# Titan_VCO.net
KiCad netlist of a schematic drawn in Altium Designer
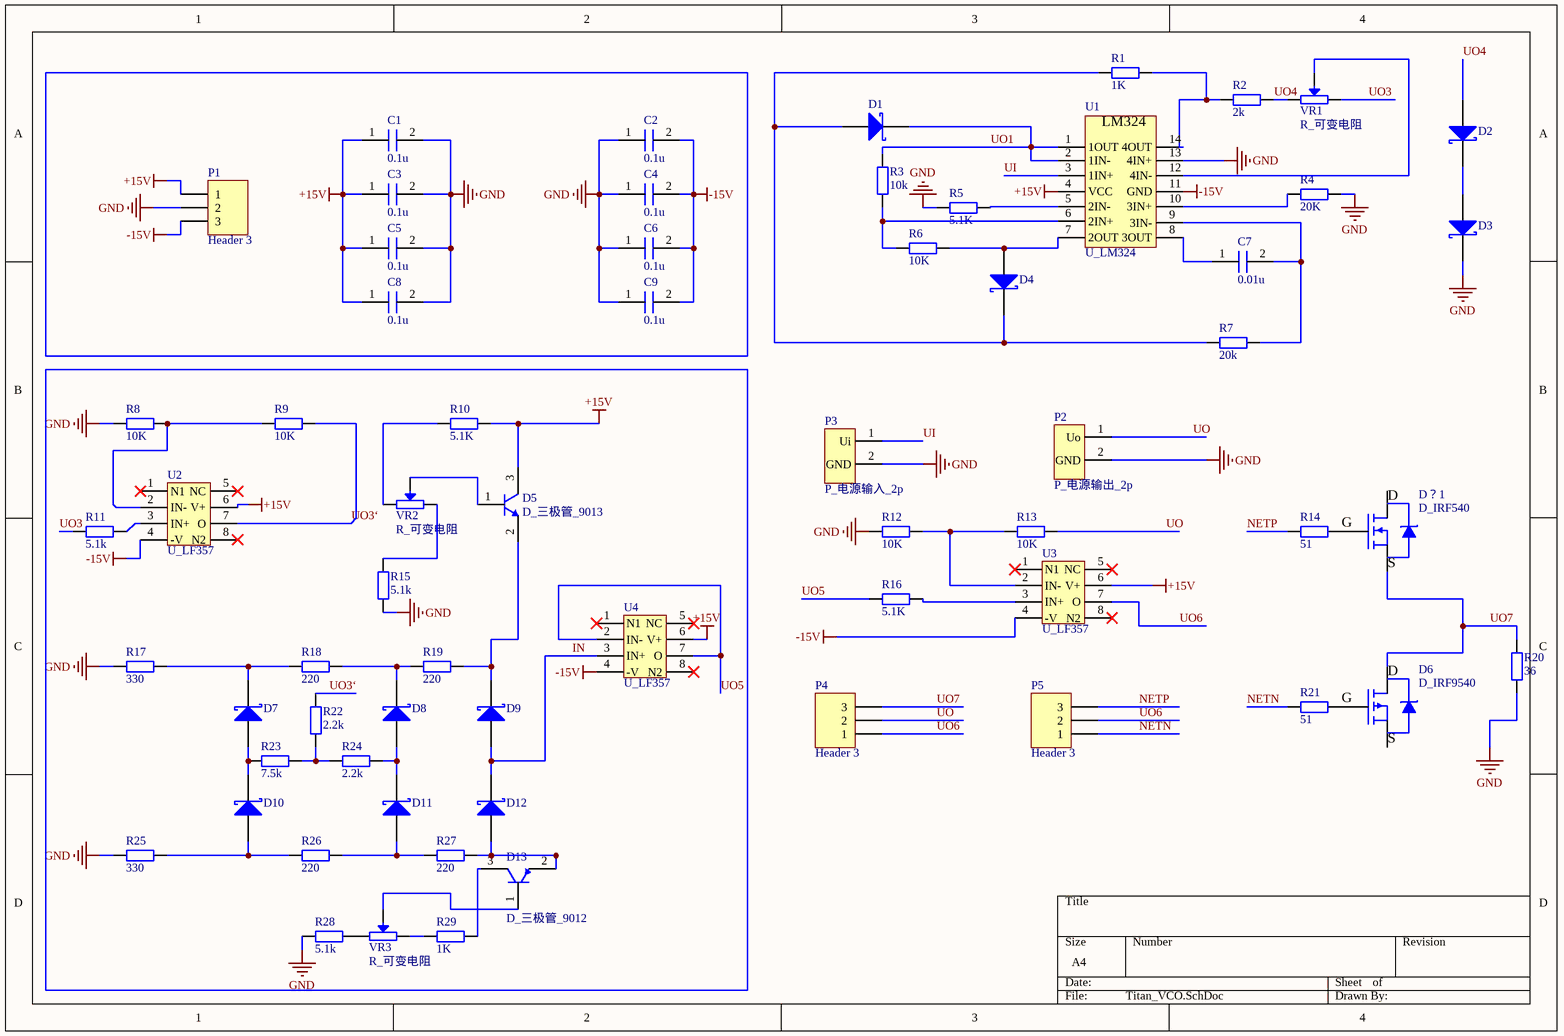
[diagram p0: Titan_VCO.SchDoc]

(export (version "E")
  (design (tool "Eeschema 10.0.6"))
  (components
    (comp (ref "C1") (value "0.1u") (footprint "C 0805_M") (libsource (lib "Titan_Schlib1") (part "C")))
    (comp (ref "C2") (value "0.1u") (footprint "C 0805_M") (libsource (lib "Titan_Schlib1") (part "C")))
    (comp (ref "C3") (value "0.1u") (footprint "C 0805_M") (libsource (lib "Titan_Schlib1") (part "C")))
    (comp (ref "C4") (value "0.1u") (footprint "C 0805_M") (libsource (lib "Titan_Schlib1") (part "C")))
    (comp (ref "C5") (value "0.1u") (footprint "C 0805_M") (libsource (lib "Titan_Schlib1") (part "C")))
    (comp (ref "C6") (value "0.1u") (footprint "C 0805_M") (libsource (lib "Titan_Schlib1") (part "C")))
    (comp (ref "C7") (value "0.01u") (footprint "C 0805_M") (libsource (lib "Titan_Schlib1") (part "C")))
    (comp (ref "C8") (value "0.1u") (footprint "C 0805_M") (libsource (lib "Titan_Schlib1") (part "C")))
    (comp (ref "C9") (value "0.1u") (footprint "C 0805_M") (libsource (lib "Titan_Schlib1") (part "C")))
    (comp (ref "D1")
      (value "D_肖特基管_稳压管")
      (footprint "TO-220AC")
      (description "Schottky Rectifier")
      (fields (field (name "PUBLISHER") "Altium Limited"))
      (libsource (lib "Titan_Schlib1") (part "D_肖特基管_稳压管"))
    )
    (comp (ref "D2")
      (value "D_肖特基管_稳压管")
      (footprint "TO-220AC")
      (description "Schottky Rectifier")
      (fields (field (name "PUBLISHER") "Altium Limited"))
      (libsource (lib "Titan_Schlib1") (part "D_肖特基管_稳压管"))
    )
    (comp (ref "D3")
      (value "D_肖特基管_稳压管")
      (footprint "TO-220AC")
      (description "Schottky Rectifier")
      (fields (field (name "PUBLISHER") "Altium Limited"))
      (libsource (lib "Titan_Schlib1") (part "D_肖特基管_稳压管"))
    )
    (comp (ref "D4")
      (value "D_肖特基管_稳压管")
      (footprint "TO-220AC")
      (description "Schottky Rectifier")
      (fields (field (name "PUBLISHER") "Altium Limited"))
      (libsource (lib "Titan_Schlib1") (part "D_肖特基管_稳压管"))
    )
    (comp (ref "D5")
      (value "D_三极管_9013")
      (footprint "D_三极管_9013")
      (libsource (lib "Titan_Schlib1") (part "D_三极管_9012"))
    )
    (comp (ref "D6")
      (value "D_IRF9540")
      (footprint "D_IRF9540")
      (libsource (lib "Titan_Schlib1") (part "D_IRF9540"))
    )
    (comp (ref "D7")
      (value "D_肖特基管_稳压管")
      (footprint "TO-220AC")
      (description "Schottky Rectifier")
      (fields (field (name "PUBLISHER") "Altium Limited"))
      (libsource (lib "Titan_Schlib1") (part "D_肖特基管_稳压管"))
    )
    (comp (ref "D8")
      (value "D_肖特基管_稳压管")
      (footprint "TO-220AC")
      (description "Schottky Rectifier")
      (fields (field (name "PUBLISHER") "Altium Limited"))
      (libsource (lib "Titan_Schlib1") (part "D_肖特基管_稳压管"))
    )
    (comp (ref "D9")
      (value "D_肖特基管_稳压管")
      (footprint "TO-220AC")
      (description "Schottky Rectifier")
      (fields (field (name "PUBLISHER") "Altium Limited"))
      (libsource (lib "Titan_Schlib1") (part "D_肖特基管_稳压管"))
    )
    (comp (ref "D10")
      (value "D_肖特基管_稳压管")
      (footprint "TO-220AC")
      (description "Schottky Rectifier")
      (fields (field (name "PUBLISHER") "Altium Limited"))
      (libsource (lib "Titan_Schlib1") (part "D_肖特基管_稳压管"))
    )
    (comp (ref "D11")
      (value "D_肖特基管_稳压管")
      (footprint "TO-220AC")
      (description "Schottky Rectifier")
      (fields (field (name "PUBLISHER") "Altium Limited"))
      (libsource (lib "Titan_Schlib1") (part "D_肖特基管_稳压管"))
    )
    (comp (ref "D12")
      (value "D_肖特基管_稳压管")
      (footprint "TO-220AC")
      (description "Schottky Rectifier")
      (fields (field (name "PUBLISHER") "Altium Limited"))
      (libsource (lib "Titan_Schlib1") (part "D_肖特基管_稳压管"))
    )
    (comp (ref "D13")
      (value "D_三极管_9012")
      (footprint "D_三极管_9012")
      (libsource (lib "") (part "D_三极管_9012_1"))
    )
    (comp (ref "D？1")
      (value "D_IRF540")
      (footprint "D_IRF540")
      (libsource (lib "Titan_Schlib1") (part "D_IRF540"))
    )
    (comp (ref "P1")
      (value "Header 3")
      (footprint "P_电源输入端子_三端口_复用")
      (description "Header, 3-Pin")
      (fields (field (name "PUBLISHER") "Altium Limited"))
      (libsource (lib "") (part "Header 3_1"))
    )
    (comp (ref "P2")
      (value "P_电源输出_2p")
      (footprint "P_电源输入端子_二端口_复用")
      (libsource (lib "Titan_Schlib1") (part "P_电源输出_2p"))
    )
    (comp (ref "P3")
      (value "P_电源输入_2p")
      (footprint "P_电源输入端子_二端口_复用")
      (libsource (lib "Titan_Schlib1") (part "P_电源输入_2p"))
    )
    (comp (ref "P4")
      (value "Header 3")
      (footprint "HDR1X3")
      (description "Header, 3-Pin")
      (fields (field (name "PUBLISHER") "Altium Limited"))
      (libsource (lib "Miscellaneous Connectors") (part "Header 3"))
    )
    (comp (ref "P5")
      (value "Header 3")
      (footprint "HDR1X3")
      (description "Header, 3-Pin")
      (fields (field (name "PUBLISHER") "Altium Limited"))
      (libsource (lib "Miscellaneous Connectors") (part "Header 3"))
    )
    (comp (ref "R1")
      (value "1K")
      (footprint "R 0805_M")
      (description "贴片电阻")
      (fields (field (name "版权归属") "黎明电子style"))
      (libsource (lib "Titan_Schlib1") (part "R1"))
    )
    (comp (ref "R2")
      (value "2k")
      (footprint "R 0805_M")
      (description "贴片电阻")
      (fields (field (name "版权归属") "黎明电子style"))
      (libsource (lib "Titan_Schlib1") (part "R1"))
    )
    (comp (ref "R3")
      (value "10k")
      (footprint "R 0805_M")
      (description "贴片电阻")
      (fields (field (name "版权归属") "黎明电子style"))
      (libsource (lib "Titan_Schlib1") (part "R1"))
    )
    (comp (ref "R4")
      (value "20K")
      (footprint "R 0805_M")
      (description "贴片电阻")
      (fields (field (name "版权归属") "黎明电子style"))
      (libsource (lib "Titan_Schlib1") (part "R1"))
    )
    (comp (ref "R5")
      (value "5.1K")
      (footprint "R 0805_M")
      (description "贴片电阻")
      (fields (field (name "版权归属") "黎明电子style"))
      (libsource (lib "Titan_Schlib1") (part "R1"))
    )
    (comp (ref "R6")
      (value "10K")
      (footprint "R 0805_M")
      (description "贴片电阻")
      (fields (field (name "版权归属") "黎明电子style"))
      (libsource (lib "Titan_Schlib1") (part "R1"))
    )
    (comp (ref "R7")
      (value "20k")
      (footprint "R 0805_M")
      (description "贴片电阻")
      (fields (field (name "版权归属") "黎明电子style"))
      (libsource (lib "Titan_Schlib1") (part "R1"))
    )
    (comp (ref "R8")
      (value "10K")
      (footprint "R 0805_M")
      (description "贴片电阻")
      (fields (field (name "版权归属") "黎明电子style"))
      (libsource (lib "Titan_Schlib1") (part "R1"))
    )
    (comp (ref "R9")
      (value "10K")
      (footprint "R 0805_M")
      (description "贴片电阻")
      (fields (field (name "版权归属") "黎明电子style"))
      (libsource (lib "Titan_Schlib1") (part "R1"))
    )
    (comp (ref "R10")
      (value "5.1K")
      (footprint "R 0805_M")
      (description "贴片电阻")
      (fields (field (name "版权归属") "黎明电子style"))
      (libsource (lib "Titan_Schlib1") (part "R1"))
    )
    (comp (ref "R11")
      (value "5.1k")
      (footprint "R 0805_M")
      (description "贴片电阻")
      (fields (field (name "版权归属") "黎明电子style"))
      (libsource (lib "Titan_Schlib1") (part "R1"))
    )
    (comp (ref "R12")
      (value "10K")
      (footprint "R 0805_M")
      (description "贴片电阻")
      (fields (field (name "版权归属") "黎明电子style"))
      (libsource (lib "Titan_Schlib1") (part "R1"))
    )
    (comp (ref "R13")
      (value "10K")
      (footprint "R 0805_M")
      (description "贴片电阻")
      (fields (field (name "版权归属") "黎明电子style"))
      (libsource (lib "Titan_Schlib1") (part "R1"))
    )
    (comp (ref "R14")
      (value "51")
      (footprint "R 0805_M")
      (description "贴片电阻")
      (fields (field (name "版权归属") "黎明电子style"))
      (libsource (lib "Titan_Schlib1") (part "R1"))
    )
    (comp (ref "R15")
      (value "5.1k")
      (footprint "R 0805_M")
      (description "贴片电阻")
      (fields (field (name "版权归属") "黎明电子style"))
      (libsource (lib "Titan_Schlib1") (part "R1"))
    )
    (comp (ref "R16")
      (value "5.1K")
      (footprint "R 0805_M")
      (description "贴片电阻")
      (fields (field (name "版权归属") "黎明电子style"))
      (libsource (lib "Titan_Schlib1") (part "R1"))
    )
    (comp (ref "R17")
      (value "330")
      (footprint "R 0805_M")
      (description "贴片电阻")
      (fields (field (name "版权归属") "黎明电子style"))
      (libsource (lib "Titan_Schlib1") (part "R1"))
    )
    (comp (ref "R18")
      (value "220")
      (footprint "R 0805_M")
      (description "贴片电阻")
      (fields (field (name "版权归属") "黎明电子style"))
      (libsource (lib "Titan_Schlib1") (part "R1"))
    )
    (comp (ref "R19")
      (value "220")
      (footprint "R 0805_M")
      (description "贴片电阻")
      (fields (field (name "版权归属") "黎明电子style"))
      (libsource (lib "Titan_Schlib1") (part "R1"))
    )
    (comp (ref "R20")
      (value "36")
      (footprint "R 0805_M")
      (description "贴片电阻")
      (fields (field (name "版权归属") "黎明电子style"))
      (libsource (lib "Titan_Schlib1") (part "R1"))
    )
    (comp (ref "R21")
      (value "51")
      (footprint "R 0805_M")
      (description "贴片电阻")
      (fields (field (name "版权归属") "黎明电子style"))
      (libsource (lib "Titan_Schlib1") (part "R1"))
    )
    (comp (ref "R22")
      (value "2.2k")
      (footprint "R 0805_M")
      (description "贴片电阻")
      (fields (field (name "版权归属") "黎明电子style"))
      (libsource (lib "Titan_Schlib1") (part "R1"))
    )
    (comp (ref "R23")
      (value "7.5k")
      (footprint "R 0805_M")
      (description "贴片电阻")
      (fields (field (name "版权归属") "黎明电子style"))
      (libsource (lib "Titan_Schlib1") (part "R1"))
    )
    (comp (ref "R24")
      (value "2.2k")
      (footprint "R 0805_M")
      (description "贴片电阻")
      (fields (field (name "版权归属") "黎明电子style"))
      (libsource (lib "Titan_Schlib1") (part "R1"))
    )
    (comp (ref "R25")
      (value "330")
      (footprint "R 0805_M")
      (description "贴片电阻")
      (fields (field (name "版权归属") "黎明电子style"))
      (libsource (lib "Titan_Schlib1") (part "R1"))
    )
    (comp (ref "R26")
      (value "220")
      (footprint "R 0805_M")
      (description "贴片电阻")
      (fields (field (name "版权归属") "黎明电子style"))
      (libsource (lib "Titan_Schlib1") (part "R1"))
    )
    (comp (ref "R27")
      (value "220")
      (footprint "R 0805_M")
      (description "贴片电阻")
      (fields (field (name "版权归属") "黎明电子style"))
      (libsource (lib "Titan_Schlib1") (part "R1"))
    )
    (comp (ref "R28")
      (value "5.1k")
      (footprint "R 0805_M")
      (description "贴片电阻")
      (fields (field (name "版权归属") "黎明电子style"))
      (libsource (lib "Titan_Schlib1") (part "R1"))
    )
    (comp (ref "R29")
      (value "1K")
      (footprint "R 0805_M")
      (description "贴片电阻")
      (fields (field (name "版权归属") "黎明电子style"))
      (libsource (lib "Titan_Schlib1") (part "R1"))
    )
    (comp (ref "U1")
      (value "U_LM324")
      (footprint "U_LM324")
      (libsource (lib "Titan_Schlib1") (part "U_LM324"))
    )
    (comp (ref "U2")
      (value "U_LF357")
      (footprint "P_DIP-8_L9.7-W6.4-P2.54-LS7.6-BL")
      (libsource (lib "Titan_Schlib1") (part "U_LF357"))
    )
    (comp (ref "U3")
      (value "U_LF357")
      (footprint "P_DIP-8_L9.7-W6.4-P2.54-LS7.6-BL")
      (libsource (lib "Titan_Schlib1") (part "U_LF357"))
    )
    (comp (ref "U4")
      (value "U_LF357")
      (footprint "P_DIP-8_L9.7-W6.4-P2.54-LS7.6-BL")
      (libsource (lib "Titan_Schlib1") (part "U_LF357"))
    )
    (comp (ref "VR1")
      (value "R_可变电阻")
      (footprint "R_微调卧式蓝白电位器")
      (libsource (lib "Titan_Schlib1") (part "R_可变电阻"))
    )
    (comp (ref "VR2")
      (value "R_可变电阻")
      (footprint "R_微调卧式蓝白电位器")
      (libsource (lib "Titan_Schlib1") (part "R_可变电阻"))
    )
    (comp (ref "VR3")
      (value "R_可变电阻")
      (footprint "R_微调卧式蓝白电位器")
      (libsource (lib "Titan_Schlib1") (part "R_可变电阻"))
    )
  )
  (nets
    (net (code "1") (name "+15V") (class "Default")
      (node (ref "C1") (pin "1") (pinfunction "1_1") (pintype "passive"))
      (node (ref "C3") (pin "1") (pinfunction "1_1") (pintype "passive"))
      (node (ref "C5") (pin "1") (pinfunction "1_1") (pintype "passive"))
      (node (ref "C8") (pin "1") (pinfunction "1_1") (pintype "passive"))
      (node (ref "D5") (pin "3") (pinfunction "c_3") (pintype "passive"))
      (node (ref "P1") (pin "1") (pinfunction "1_1") (pintype "passive"))
      (node (ref "R10") (pin "2") (pinfunction "2_2") (pintype "passive"))
      (node (ref "U1") (pin "4") (pinfunction "VCC_4") (pintype "passive"))
      (node (ref "U2") (pin "6") (pinfunction "V+_6") (pintype "passive"))
      (node (ref "U3") (pin "6") (pinfunction "V+_6") (pintype "passive"))
      (node (ref "U4") (pin "6") (pinfunction "V+_6") (pintype "passive"))
    )
    (net (code "2") (name "-15V") (class "Default")
      (node (ref "C2") (pin "2") (pinfunction "2_2") (pintype "passive"))
      (node (ref "C4") (pin "2") (pinfunction "2_2") (pintype "passive"))
      (node (ref "C6") (pin "2") (pinfunction "2_2") (pintype "passive"))
      (node (ref "C9") (pin "2") (pinfunction "2_2") (pintype "passive"))
      (node (ref "P1") (pin "3") (pinfunction "3_3") (pintype "passive"))
      (node (ref "U1") (pin "11") (pinfunction "GND_11") (pintype "passive"))
      (node (ref "U2") (pin "4") (pinfunction "-V_4") (pintype "passive"))
      (node (ref "U3") (pin "4") (pinfunction "-V_4") (pintype "passive"))
      (node (ref "U4") (pin "4") (pinfunction "-V_4") (pintype "passive"))
    )
    (net (code "3") (name "/IN") (class "Default")
      (node (ref "D12") (pin "1") (pinfunction "K_1") (pintype "passive"))
      (node (ref "D9") (pin "3") (pinfunction "A_3") (pintype "passive"))
      (node (ref "U4") (pin "3") (pinfunction "IN+_3") (pintype "passive"))
    )
    (net (code "4") (name "/NETN") (class "Default")
      (node (ref "P5") (pin "1") (pinfunction "1_1") (pintype "passive"))
      (node (ref "R21") (pin "2") (pinfunction "2_2") (pintype "passive"))
    )
    (net (code "5") (name "/NETP") (class "Default")
      (node (ref "P5") (pin "3") (pinfunction "3_3") (pintype "passive"))
      (node (ref "R14") (pin "2") (pinfunction "2_2") (pintype "passive"))
    )
    (net (code "6") (name "/UI") (class "Default")
      (node (ref "P3") (pin "1") (pinfunction "Ui_1") (pintype "passive"))
      (node (ref "U1") (pin "3") (pinfunction "1IN+_3") (pintype "passive"))
    )
    (net (code "7") (name "/UO") (class "Default")
      (node (ref "P2") (pin "1") (pinfunction "Uo_1") (pintype "passive"))
      (node (ref "P4") (pin "2") (pinfunction "2_2") (pintype "passive"))
      (node (ref "R13") (pin "1") (pinfunction "1_1") (pintype "passive"))
    )
    (net (code "8") (name "/UO1") (class "Default")
      (node (ref "D1") (pin "1") (pinfunction "K_1") (pintype "passive"))
      (node (ref "R3") (pin "2") (pinfunction "2_2") (pintype "passive"))
      (node (ref "U1") (pin "1") (pinfunction "1OUT_1") (pintype "passive"))
      (node (ref "U1") (pin "2") (pinfunction "1IN-_2") (pintype "passive"))
    )
    (net (code "9") (name "/UO3") (class "Default")
      (node (ref "R11") (pin "1") (pinfunction "1_1") (pintype "passive"))
      (node (ref "VR1") (pin "3") (pinfunction "2_3") (pintype "passive"))
    )
    (net (code "10") (name "/UO3‘") (class "Default")
      (node (ref "R22") (pin "2") (pinfunction "2_2") (pintype "passive"))
      (node (ref "R9") (pin "2") (pinfunction "2_2") (pintype "passive"))
      (node (ref "U2") (pin "7") (pinfunction "O_7") (pintype "passive"))
    )
    (net (code "11") (name "/UO4") (class "Default")
      (node (ref "D2") (pin "3") (pinfunction "A_3") (pintype "passive"))
      (node (ref "R2") (pin "1") (pinfunction "1_1") (pintype "passive"))
      (node (ref "VR1") (pin "1") (pinfunction "1_1") (pintype "passive"))
    )
    (net (code "12") (name "/UO5") (class "Default")
      (node (ref "R16") (pin "2") (pinfunction "2_2") (pintype "passive"))
      (node (ref "U4") (pin "2") (pinfunction "IN-_2") (pintype "passive"))
      (node (ref "U4") (pin "7") (pinfunction "O_7") (pintype "passive"))
    )
    (net (code "13") (name "/UO6") (class "Default")
      (node (ref "P4") (pin "1") (pinfunction "1_1") (pintype "passive"))
      (node (ref "P5") (pin "2") (pinfunction "2_2") (pintype "passive"))
      (node (ref "U3") (pin "7") (pinfunction "O_7") (pintype "passive"))
    )
    (net (code "14") (name "/UO7") (class "Default")
      (node (ref "D6") (pin "2") (pinfunction "D_2") (pintype "passive"))
      (node (ref "D？1") (pin "3") (pinfunction "S_3") (pintype "passive"))
      (node (ref "P4") (pin "3") (pinfunction "3_3") (pintype "passive"))
      (node (ref "R20") (pin "1") (pinfunction "1_1") (pintype "passive"))
    )
    (net (code "15") (name "GND") (class "Default")
      (node (ref "C1") (pin "2") (pinfunction "2_2") (pintype "passive"))
      (node (ref "C2") (pin "1") (pinfunction "1_1") (pintype "passive"))
      (node (ref "C3") (pin "2") (pinfunction "2_2") (pintype "passive"))
      (node (ref "C4") (pin "1") (pinfunction "1_1") (pintype "passive"))
      (node (ref "C5") (pin "2") (pinfunction "2_2") (pintype "passive"))
      (node (ref "C6") (pin "1") (pinfunction "1_1") (pintype "passive"))
      (node (ref "C8") (pin "2") (pinfunction "2_2") (pintype "passive"))
      (node (ref "C9") (pin "1") (pinfunction "1_1") (pintype "passive"))
      (node (ref "D3") (pin "1") (pinfunction "K_1") (pintype "passive"))
      (node (ref "P1") (pin "2") (pinfunction "2_2") (pintype "passive"))
      (node (ref "P2") (pin "2") (pinfunction "GND_2") (pintype "passive"))
      (node (ref "P3") (pin "2") (pinfunction "GND_2") (pintype "passive"))
      (node (ref "R12") (pin "2") (pinfunction "2_2") (pintype "passive"))
      (node (ref "R15") (pin "1") (pinfunction "1_1") (pintype "passive"))
      (node (ref "R17") (pin "1") (pinfunction "1_1") (pintype "passive"))
      (node (ref "R20") (pin "2") (pinfunction "2_2") (pintype "passive"))
      (node (ref "R25") (pin "1") (pinfunction "1_1") (pintype "passive"))
      (node (ref "R28") (pin "1") (pinfunction "1_1") (pintype "passive"))
      (node (ref "R4") (pin "1") (pinfunction "1_1") (pintype "passive"))
      (node (ref "R5") (pin "2") (pinfunction "2_2") (pintype "passive"))
      (node (ref "R8") (pin "1") (pinfunction "1_1") (pintype "passive"))
      (node (ref "U1") (pin "13") (pinfunction "4IN+_13") (pintype "passive"))
    )
    (net (code "16") (name "Net-(D1-A)") (class "Default")
      (node (ref "D1") (pin "3") (pinfunction "A_3") (pintype "passive"))
      (node (ref "D4") (pin "1") (pinfunction "K_1") (pintype "passive"))
      (node (ref "R1") (pin "2") (pinfunction "2_2") (pintype "passive"))
      (node (ref "R7") (pin "2") (pinfunction "2_2") (pintype "passive"))
    )
    (net (code "17") (name "Net-(D2-K)") (class "Default")
      (node (ref "D2") (pin "1") (pinfunction "K_1") (pintype "passive"))
      (node (ref "D3") (pin "3") (pinfunction "A_3") (pintype "passive"))
    )
    (net (code "18") (name "Net-(D4-A)") (class "Default")
      (node (ref "D4") (pin "3") (pinfunction "A_3") (pintype "passive"))
      (node (ref "R6") (pin "1") (pinfunction "1_1") (pintype "passive"))
      (node (ref "U1") (pin "7") (pinfunction "2OUT_7") (pintype "passive"))
    )
    (net (code "19") (name "Net-(D5-b)") (class "Default")
      (node (ref "D5") (pin "1") (pinfunction "b_1") (pintype "passive"))
      (node (ref "VR2") (pin "2") (pinfunction "2_2") (pintype "passive"))
    )
    (net (code "20") (name "Net-(D5-e)") (class "Default")
      (node (ref "D5") (pin "2") (pinfunction "e_2") (pintype "passive"))
      (node (ref "D9") (pin "1") (pinfunction "K_1") (pintype "passive"))
      (node (ref "R19") (pin "2") (pinfunction "2_2") (pintype "passive"))
    )
    (net (code "21") (name "Net-(D6-G)") (class "Default")
      (node (ref "D6") (pin "1") (pinfunction "G_1") (pintype "passive"))
      (node (ref "R21") (pin "1") (pinfunction "1_1") (pintype "passive"))
    )
    (net (code "22") (name "Net-(D7-K)") (class "Default")
      (node (ref "D7") (pin "1") (pinfunction "K_1") (pintype "passive"))
      (node (ref "R17") (pin "2") (pinfunction "2_2") (pintype "passive"))
      (node (ref "R18") (pin "1") (pinfunction "1_1") (pintype "passive"))
    )
    (net (code "23") (name "Net-(D8-K)") (class "Default")
      (node (ref "D8") (pin "1") (pinfunction "K_1") (pintype "passive"))
      (node (ref "R18") (pin "2") (pinfunction "2_2") (pintype "passive"))
      (node (ref "R19") (pin "1") (pinfunction "1_1") (pintype "passive"))
    )
    (net (code "24") (name "Net-(D10-A)") (class "Default")
      (node (ref "D10") (pin "3") (pinfunction "A_3") (pintype "passive"))
      (node (ref "R25") (pin "2") (pinfunction "2_2") (pintype "passive"))
      (node (ref "R26") (pin "1") (pinfunction "1_1") (pintype "passive"))
    )
    (net (code "25") (name "Net-(D10-K)") (class "Default")
      (node (ref "D10") (pin "1") (pinfunction "K_1") (pintype "passive"))
      (node (ref "D7") (pin "3") (pinfunction "A_3") (pintype "passive"))
      (node (ref "R23") (pin "2") (pinfunction "2_2") (pintype "passive"))
    )
    (net (code "26") (name "Net-(D11-A)") (class "Default")
      (node (ref "D11") (pin "3") (pinfunction "A_3") (pintype "passive"))
      (node (ref "R26") (pin "2") (pinfunction "2_2") (pintype "passive"))
      (node (ref "R27") (pin "1") (pinfunction "1_1") (pintype "passive"))
    )
    (net (code "27") (name "Net-(D11-K)") (class "Default")
      (node (ref "D11") (pin "1") (pinfunction "K_1") (pintype "passive"))
      (node (ref "D8") (pin "3") (pinfunction "A_3") (pintype "passive"))
      (node (ref "R24") (pin "2") (pinfunction "2_2") (pintype "passive"))
    )
    (net (code "28") (name "Net-(D12-A)") (class "Default")
      (node (ref "D12") (pin "3") (pinfunction "A_3") (pintype "passive"))
      (node (ref "D13") (pin "2") (pinfunction "e_2") (pintype "passive"))
      (node (ref "R27") (pin "2") (pinfunction "2_2") (pintype "passive"))
    )
    (net (code "29") (name "Net-(D13-b)") (class "Default")
      (node (ref "D13") (pin "1") (pinfunction "b_1") (pintype "passive"))
      (node (ref "VR3") (pin "2") (pinfunction "2_2") (pintype "passive"))
    )
    (net (code "30") (name "Net-(D13-c)") (class "Default")
      (node (ref "D13") (pin "3") (pinfunction "c_3") (pintype "passive"))
      (node (ref "R29") (pin "2") (pinfunction "2_2") (pintype "passive"))
    )
    (net (code "31") (name "Net-(D？1-G)") (class "Default")
      (node (ref "D？1") (pin "1") (pinfunction "G_1") (pintype "passive"))
      (node (ref "R14") (pin "1") (pinfunction "1_1") (pintype "passive"))
    )
    (net (code "32") (name "Net-(R10-Pad1)") (class "Default")
      (node (ref "R10") (pin "1") (pinfunction "1_1") (pintype "passive"))
      (node (ref "VR2") (pin "1") (pinfunction "1_1") (pintype "passive"))
    )
    (net (code "33") (name "Net-(R15-Pad2)") (class "Default")
      (node (ref "R15") (pin "2") (pinfunction "2_2") (pintype "passive"))
      (node (ref "VR2") (pin "3") (pinfunction "2_3") (pintype "passive"))
    )
    (net (code "34") (name "Net-(R22-Pad1)") (class "Default")
      (node (ref "R22") (pin "1") (pinfunction "1_1") (pintype "passive"))
      (node (ref "R23") (pin "1") (pinfunction "1_1") (pintype "passive"))
      (node (ref "R24") (pin "1") (pinfunction "1_1") (pintype "passive"))
    )
    (net (code "35") (name "Net-(R28-Pad2)") (class "Default")
      (node (ref "R28") (pin "2") (pinfunction "2_2") (pintype "passive"))
      (node (ref "VR3") (pin "1") (pinfunction "1_1") (pintype "passive"))
    )
    (net (code "36") (name "Net-(R29-Pad1)") (class "Default")
      (node (ref "R29") (pin "1") (pinfunction "1_1") (pintype "passive"))
      (node (ref "VR3") (pin "3") (pinfunction "2_3") (pintype "passive"))
    )
    (net (code "37") (name "Net-(U1-2IN+)") (class "Default")
      (node (ref "R3") (pin "1") (pinfunction "1_1") (pintype "passive"))
      (node (ref "R6") (pin "2") (pinfunction "2_2") (pintype "passive"))
      (node (ref "U1") (pin "6") (pinfunction "2IN+_6") (pintype "passive"))
    )
    (net (code "38") (name "Net-(U1-2IN-)") (class "Default")
      (node (ref "R5") (pin "1") (pinfunction "1_1") (pintype "passive"))
      (node (ref "U1") (pin "5") (pinfunction "2IN-_5") (pintype "passive"))
    )
    (net (code "39") (name "Net-(U1-3IN+)") (class "Default")
      (node (ref "R4") (pin "2") (pinfunction "2_2") (pintype "passive"))
      (node (ref "U1") (pin "10") (pinfunction "3IN+_10") (pintype "passive"))
    )
    (net (code "40") (name "Net-(U1-3IN-)") (class "Default")
      (node (ref "C7") (pin "2") (pinfunction "2_2") (pintype "passive"))
      (node (ref "R7") (pin "1") (pinfunction "1_1") (pintype "passive"))
      (node (ref "U1") (pin "9") (pinfunction "3IN-_9") (pintype "passive"))
    )
    (net (code "41") (name "Net-(U1-3OUT)") (class "Default")
      (node (ref "C7") (pin "1") (pinfunction "1_1") (pintype "passive"))
      (node (ref "U1") (pin "8") (pinfunction "3OUT_8") (pintype "passive"))
    )
    (net (code "42") (name "Net-(U1-4IN-)") (class "Default")
      (node (ref "U1") (pin "12") (pinfunction "4IN-_12") (pintype "passive"))
      (node (ref "VR1") (pin "2") (pinfunction "2_2") (pintype "passive"))
    )
    (net (code "43") (name "Net-(U1-4OUT)") (class "Default")
      (node (ref "R1") (pin "1") (pinfunction "1_1") (pintype "passive"))
      (node (ref "R2") (pin "2") (pinfunction "2_2") (pintype "passive"))
      (node (ref "U1") (pin "14") (pinfunction "4OUT_14") (pintype "passive"))
    )
    (net (code "44") (name "Net-(U2-IN+)") (class "Default")
      (node (ref "R11") (pin "2") (pinfunction "2_2") (pintype "passive"))
      (node (ref "U2") (pin "3") (pinfunction "IN+_3") (pintype "passive"))
    )
    (net (code "45") (name "Net-(U2-IN-)") (class "Default")
      (node (ref "R8") (pin "2") (pinfunction "2_2") (pintype "passive"))
      (node (ref "R9") (pin "1") (pinfunction "1_1") (pintype "passive"))
      (node (ref "U2") (pin "2") (pinfunction "IN-_2") (pintype "passive"))
    )
    (net (code "46") (name "Net-(U3-IN+)") (class "Default")
      (node (ref "R16") (pin "1") (pinfunction "1_1") (pintype "passive"))
      (node (ref "U3") (pin "3") (pinfunction "IN+_3") (pintype "passive"))
    )
    (net (code "47") (name "Net-(U3-IN-)") (class "Default")
      (node (ref "R12") (pin "1") (pinfunction "1_1") (pintype "passive"))
      (node (ref "R13") (pin "2") (pinfunction "2_2") (pintype "passive"))
      (node (ref "U3") (pin "2") (pinfunction "IN-_2") (pintype "passive"))
    )
    (net (code "48") (name "unconnected-(D6-S-Pad3)") (class "Default")
      (node (ref "D6") (pin "3") (pinfunction "S_3") (pintype "passive"))
    )
    (net (code "49") (name "unconnected-(D？1-D-Pad2)") (class "Default")
      (node (ref "D？1") (pin "2") (pinfunction "D_2") (pintype "passive"))
    )
    (net (code "50") (name "unconnected-(U2-N1-Pad1)") (class "Default")
      (node (ref "U2") (pin "1") (pinfunction "N1_1") (pintype "passive+no_connect"))
    )
    (net (code "51") (name "unconnected-(U2-N2-Pad8)") (class "Default")
      (node (ref "U2") (pin "8") (pinfunction "N2_8") (pintype "passive+no_connect"))
    )
    (net (code "52") (name "unconnected-(U2-NC-Pad5)") (class "Default")
      (node (ref "U2") (pin "5") (pinfunction "NC_5") (pintype "passive+no_connect"))
    )
    (net (code "53") (name "unconnected-(U3-N1-Pad1)") (class "Default")
      (node (ref "U3") (pin "1") (pinfunction "N1_1") (pintype "passive+no_connect"))
    )
    (net (code "54") (name "unconnected-(U3-N2-Pad8)") (class "Default")
      (node (ref "U3") (pin "8") (pinfunction "N2_8") (pintype "passive+no_connect"))
    )
    (net (code "55") (name "unconnected-(U3-NC-Pad5)") (class "Default")
      (node (ref "U3") (pin "5") (pinfunction "NC_5") (pintype "passive+no_connect"))
    )
    (net (code "56") (name "unconnected-(U4-N1-Pad1)") (class "Default")
      (node (ref "U4") (pin "1") (pinfunction "N1_1") (pintype "passive+no_connect"))
    )
    (net (code "57") (name "unconnected-(U4-N2-Pad8)") (class "Default")
      (node (ref "U4") (pin "8") (pinfunction "N2_8") (pintype "passive+no_connect"))
    )
    (net (code "58") (name "unconnected-(U4-NC-Pad5)") (class "Default")
      (node (ref "U4") (pin "5") (pinfunction "NC_5") (pintype "passive+no_connect"))
    )
  )
)
